# GateWay-NRF-version.net
KiCad netlist of a schematic drawn in Altium Designer
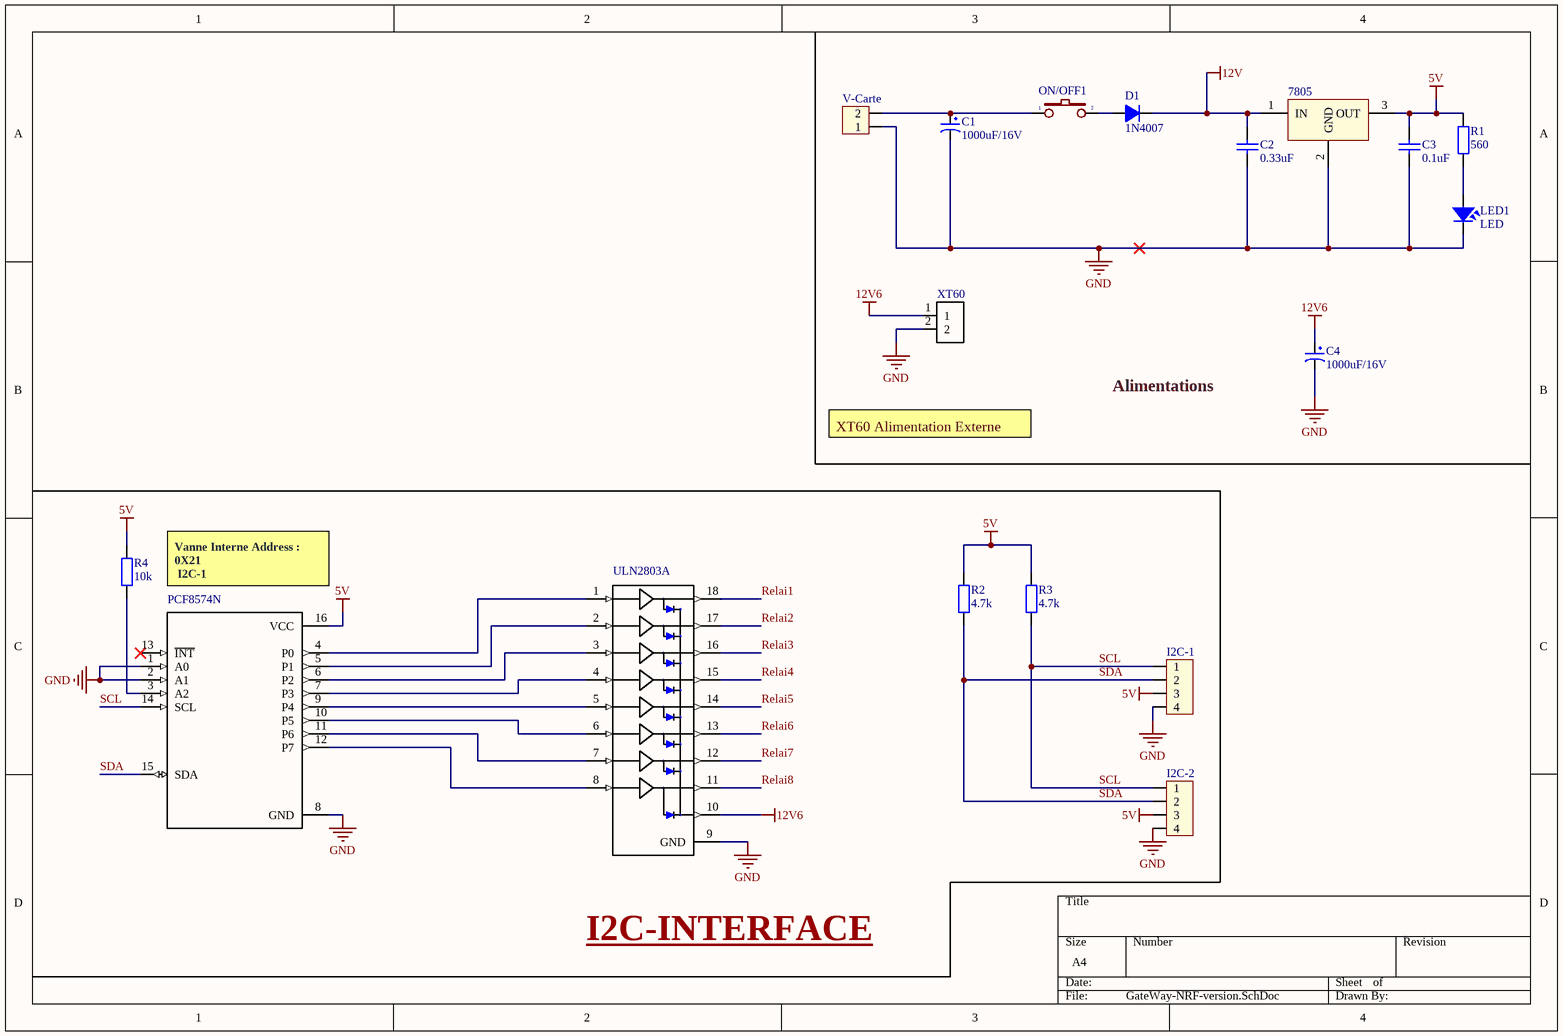
[diagram p0: GateWay-NRF-version.SchDoc]

(export (version "E")
  (design (tool "Eeschema 10.0.6"))
  (components
    (comp (ref "7805")
      (value "LM7805")
      (footprint "QTO-220")
      (description "On ap +, from + 5 to + 24VDC")
      (libsource (lib "hphonglib") (part "LM78xx_1"))
    )
    (comp (ref "C1")
      (value "1000uF/16V")
      (footprint "CP1.5/3.4")
      (description "Cap 1000uF/16V - 220uF/50V")
      (libsource (lib "hphonglib") (part "CP4"))
    )
    (comp (ref "C2")
      (value "0.33uF")
      (footprint "Cap Non-Pol 3mm")
      (description "Non-polarized Capacitor")
      (fields (field (name "Comment") "Cap Non-pol") (field (name "PUBLISHER") "Altium Limited"))
      (libsource (lib "hphonglib") (part "Cap Non-pol"))
    )
    (comp (ref "C3")
      (value "0.1uF")
      (footprint "Cap Non-Pol 3mm")
      (description "Non-polarized Capacitor")
      (fields (field (name "Comment") "Cap Non-pol") (field (name "PUBLISHER") "Altium Limited"))
      (libsource (lib "hphonglib") (part "Cap Non-pol"))
    )
    (comp (ref "C4")
      (value "1000uF/16V")
      (footprint "CP1.5/3.4")
      (description "Cap 1000uF/16V - 220uF/50V")
      (libsource (lib "hphonglib") (part "CP4"))
    )
    (comp (ref "D1")
      (value "1N4007")
      (footprint "D1A")
      (description "Diode 1A")
      (libsource (lib "hphonglib") (part "D1A"))
    )
    (comp (ref "I2C-1")
      (value "I2C")
      (footprint "CON4")
      (description "Connector 4")
      (libsource (lib "hphonglib") (part "Con4"))
    )
    (comp (ref "I2C-2")
      (value "I2C")
      (footprint "CON4")
      (description "Connector 4")
      (libsource (lib "hphonglib") (part "Con4"))
    )
    (comp (ref "LED1")
      (value "LED")
      (footprint "LED-3")
      (description "LED Single colour Green and Red")
      (libsource (lib "hanguyen") (part "LED"))
    )
    (comp (ref "ON/OFF1")
      (value "ON/OFF")
      (footprint "SW2")
      (description "Switch button 2 pin")
      (libsource (lib "hphonglib") (part "SW2"))
    )
    (comp (ref "PCF8574N")
      (value "PCF8574N")
      (footprint "*DIP794W45P254L1969H508Q16")
      (description "Remote 8-Bit I/O Expander for I2C-Bus 16-PDIP -40 to 85")
      (fields
        (field (name "BUYPART") "https://www.snapeda.com/parts/PCF8574N/Texas%20Instruments/view-part/271889/?ref=eda")
        (field (name "MF") "Texas Instruments")
      )
      (libsource (lib "PCF8574N") (part "PCF8574N"))
    )
    (comp (ref "R1")
      (value "560")
      (footprint "R1/4W")
      (description "Resistor 1/4W")
      (libsource (lib "hanguyen") (part "R1/4W"))
    )
    (comp (ref "R2")
      (value "4.7k")
      (footprint "R1/4W")
      (description "Resistor 1/4W")
      (libsource (lib "hanguyen") (part "R1/4W"))
    )
    (comp (ref "R3")
      (value "4.7k")
      (footprint "R1/4W")
      (description "Resistor 1/4W")
      (libsource (lib "hanguyen") (part "R1/4W"))
    )
    (comp (ref "R4")
      (value "10k")
      (footprint "R1/4W")
      (description "Resistor 1/4W")
      (libsource (lib "hanguyen") (part "R1/4W"))
    )
    (comp (ref "ULN2803A")
      (value "ULN2803A")
      (footprint "*DIP850W46P254L2324H393Q18")
      (description "Bipolar (BJT) Transistor Array 8 NPN Darlington 50V 500mA 2.25W Through Hole 18-DIP")
      (fields (field (name "MF") "STMicroelectronics") (field (name "DIGI-KEY_PART_NUMBER") "497-2356-5-ND"))
      (libsource (lib "ULN2803A") (part "ULN2803A"))
    )
    (comp (ref "V-Carte")
      (value "Header 2")
      (footprint "HED2")
      (description "Header 2 (Green)")
      (libsource (lib "hanguyen") (part "Hed2"))
    )
    (comp (ref "XT60")
      (value "XT60_YELLOW")
      (footprint "*AMASS_XT60PB-M")
      (description "Power connector; 65A; PIN: 2; Colour: yellow-Male")
      (fields (field (name "MP") "XT60 YELLOW") (field (name "MF") "Pololu"))
      (libsource (lib "XT60") (part "XT60"))
    )
  )
  (nets
    (net (code "1") (name "/Relai1") (class "Default")
      (node (ref "ULN2803A") (pin "18") (pinfunction "OUT_1_18") (pintype "output"))
    )
    (net (code "2") (name "/Relai2") (class "Default")
      (node (ref "ULN2803A") (pin "17") (pinfunction "OUT_2_17") (pintype "output"))
    )
    (net (code "3") (name "/Relai3") (class "Default")
      (node (ref "ULN2803A") (pin "16") (pinfunction "OUT_3_16") (pintype "output"))
    )
    (net (code "4") (name "/Relai4") (class "Default")
      (node (ref "ULN2803A") (pin "15") (pinfunction "OUT_4_15") (pintype "output"))
    )
    (net (code "5") (name "/Relai5") (class "Default")
      (node (ref "ULN2803A") (pin "14") (pinfunction "OUT_5_14") (pintype "output"))
    )
    (net (code "6") (name "/Relai6") (class "Default")
      (node (ref "ULN2803A") (pin "13") (pinfunction "OUT_6_13") (pintype "output"))
    )
    (net (code "7") (name "/Relai7") (class "Default")
      (node (ref "ULN2803A") (pin "12") (pinfunction "OUT_7_12") (pintype "output"))
    )
    (net (code "8") (name "/Relai8") (class "Default")
      (node (ref "ULN2803A") (pin "11") (pinfunction "OUT_8_11") (pintype "output"))
    )
    (net (code "9") (name "/SCL") (class "Default")
      (node (ref "I2C-1") (pin "1") (pinfunction "1_1") (pintype "passive"))
      (node (ref "I2C-2") (pin "1") (pinfunction "1_1") (pintype "passive"))
      (node (ref "PCF8574N") (pin "14") (pinfunction "SCL_14") (pintype "input"))
      (node (ref "R3") (pin "1") (pinfunction "1_1") (pintype "passive"))
    )
    (net (code "10") (name "/SDA") (class "Default")
      (node (ref "I2C-1") (pin "2") (pinfunction "2_2") (pintype "passive"))
      (node (ref "I2C-2") (pin "2") (pinfunction "2_2") (pintype "passive"))
      (node (ref "PCF8574N") (pin "15") (pinfunction "SDA_15") (pintype "bidirectional"))
      (node (ref "R2") (pin "1") (pinfunction "1_1") (pintype "passive"))
    )
    (net (code "11") (name "5V") (class "Default")
      (node (ref "7805") (pin "3") (pinfunction "OUT_3") (pintype "passive"))
      (node (ref "C3") (pin "2") (pinfunction "2_2") (pintype "passive"))
      (node (ref "I2C-1") (pin "3") (pinfunction "3_3") (pintype "passive"))
      (node (ref "I2C-2") (pin "3") (pinfunction "3_3") (pintype "passive"))
      (node (ref "PCF8574N") (pin "16") (pinfunction "VCC_16") (pintype "power_in"))
      (node (ref "R1") (pin "1") (pinfunction "1_1") (pintype "passive"))
      (node (ref "R2") (pin "2") (pinfunction "2_2") (pintype "passive"))
      (node (ref "R3") (pin "2") (pinfunction "2_2") (pintype "passive"))
      (node (ref "R4") (pin "2") (pinfunction "2_2") (pintype "passive"))
    )
    (net (code "12") (name "12V") (class "Default")
      (node (ref "7805") (pin "1") (pinfunction "IN_1") (pintype "passive"))
      (node (ref "C2") (pin "2") (pinfunction "2_2") (pintype "passive"))
      (node (ref "D1") (pin "2") (pinfunction "K_2") (pintype "passive"))
    )
    (net (code "13") (name "12V6") (class "Default")
      (node (ref "C4") (pin "1") (pinfunction "1_1") (pintype "passive"))
      (node (ref "ULN2803A") (pin "10") (pinfunction "COMMON_10") (pintype "output"))
      (node (ref "XT60") (pin "1") (pinfunction "1_1") (pintype "passive"))
    )
    (net (code "14") (name "GND") (class "Default")
      (node (ref "7805") (pin "2") (pinfunction "GND_2") (pintype "passive"))
      (node (ref "C1") (pin "2") (pinfunction "2_2") (pintype "passive"))
      (node (ref "C2") (pin "1") (pinfunction "1_1") (pintype "passive"))
      (node (ref "C3") (pin "1") (pinfunction "1_1") (pintype "passive"))
      (node (ref "C4") (pin "2") (pinfunction "2_2") (pintype "passive"))
      (node (ref "I2C-1") (pin "4") (pinfunction "4_4") (pintype "passive"))
      (node (ref "I2C-2") (pin "4") (pinfunction "4_4") (pintype "passive"))
      (node (ref "LED1") (pin "2") (pinfunction "2_2") (pintype "passive"))
      (node (ref "PCF8574N") (pin "1") (pinfunction "A0_1") (pintype "input"))
      (node (ref "PCF8574N") (pin "2") (pinfunction "A1_2") (pintype "input"))
      (node (ref "PCF8574N") (pin "8") (pinfunction "GND_8") (pintype "power_in"))
      (node (ref "ULN2803A") (pin "9") (pinfunction "GND_9") (pintype "power_in"))
      (node (ref "V-Carte") (pin "1") (pinfunction "1_1") (pintype "passive"))
      (node (ref "XT60") (pin "2") (pinfunction "2_2") (pintype "passive"))
    )
    (net (code "15") (name "Net-(C1-Pad1)") (class "Default")
      (node (ref "C1") (pin "1") (pinfunction "1_1") (pintype "passive"))
      (node (ref "ON/OFF1") (pin "1") (pinfunction "1_1") (pintype "passive"))
      (node (ref "V-Carte") (pin "2") (pinfunction "2_2") (pintype "passive"))
    )
    (net (code "16") (name "Net-(D1-A)") (class "Default")
      (node (ref "D1") (pin "1") (pinfunction "A_1") (pintype "passive"))
      (node (ref "ON/OFF1") (pin "2") (pinfunction "2_2") (pintype "passive"))
    )
    (net (code "17") (name "Net-(LED1-Pad1)") (class "Default")
      (node (ref "LED1") (pin "1") (pinfunction "1_1") (pintype "passive"))
      (node (ref "R1") (pin "2") (pinfunction "2_2") (pintype "passive"))
    )
    (net (code "18") (name "Net-(PCF8574N-A2)") (class "Default")
      (node (ref "PCF8574N") (pin "3") (pinfunction "A2_3") (pintype "input"))
      (node (ref "R4") (pin "1") (pinfunction "1_1") (pintype "passive"))
    )
    (net (code "19") (name "Net-(PCF8574N-P0)") (class "Default")
      (node (ref "PCF8574N") (pin "4") (pinfunction "P0_4") (pintype "output"))
      (node (ref "ULN2803A") (pin "1") (pinfunction "IN_1_1") (pintype "input"))
    )
    (net (code "20") (name "Net-(PCF8574N-P1)") (class "Default")
      (node (ref "PCF8574N") (pin "5") (pinfunction "P1_5") (pintype "output"))
      (node (ref "ULN2803A") (pin "2") (pinfunction "IN_2_2") (pintype "input"))
    )
    (net (code "21") (name "Net-(PCF8574N-P2)") (class "Default")
      (node (ref "PCF8574N") (pin "6") (pinfunction "P2_6") (pintype "output"))
      (node (ref "ULN2803A") (pin "3") (pinfunction "IN_3_3") (pintype "input"))
    )
    (net (code "22") (name "Net-(PCF8574N-P3)") (class "Default")
      (node (ref "PCF8574N") (pin "7") (pinfunction "P3_7") (pintype "output"))
      (node (ref "ULN2803A") (pin "4") (pinfunction "IN_4_4") (pintype "input"))
    )
    (net (code "23") (name "Net-(PCF8574N-P4)") (class "Default")
      (node (ref "PCF8574N") (pin "9") (pinfunction "P4_9") (pintype "output"))
      (node (ref "ULN2803A") (pin "5") (pinfunction "IN_5_5") (pintype "input"))
    )
    (net (code "24") (name "Net-(PCF8574N-P5)") (class "Default")
      (node (ref "PCF8574N") (pin "10") (pinfunction "P5_10") (pintype "output"))
      (node (ref "ULN2803A") (pin "6") (pinfunction "IN_6_6") (pintype "input"))
    )
    (net (code "25") (name "Net-(PCF8574N-P6)") (class "Default")
      (node (ref "PCF8574N") (pin "11") (pinfunction "P6_11") (pintype "output"))
      (node (ref "ULN2803A") (pin "7") (pinfunction "IN_7_7") (pintype "input"))
    )
    (net (code "26") (name "Net-(PCF8574N-P7)") (class "Default")
      (node (ref "PCF8574N") (pin "12") (pinfunction "P7_12") (pintype "output"))
      (node (ref "ULN2803A") (pin "8") (pinfunction "IN_8_8") (pintype "input"))
    )
    (net (code "27") (name "unconnected-(PCF8574N-~{INT}-Pad13)") (class "Default")
      (node (ref "PCF8574N") (pin "13") (pinfunction "~{INT}_13") (pintype "input+no_connect"))
    )
  )
)
